# IAQ_Schematic.net
KiCad netlist of a schematic drawn in Altium Designer
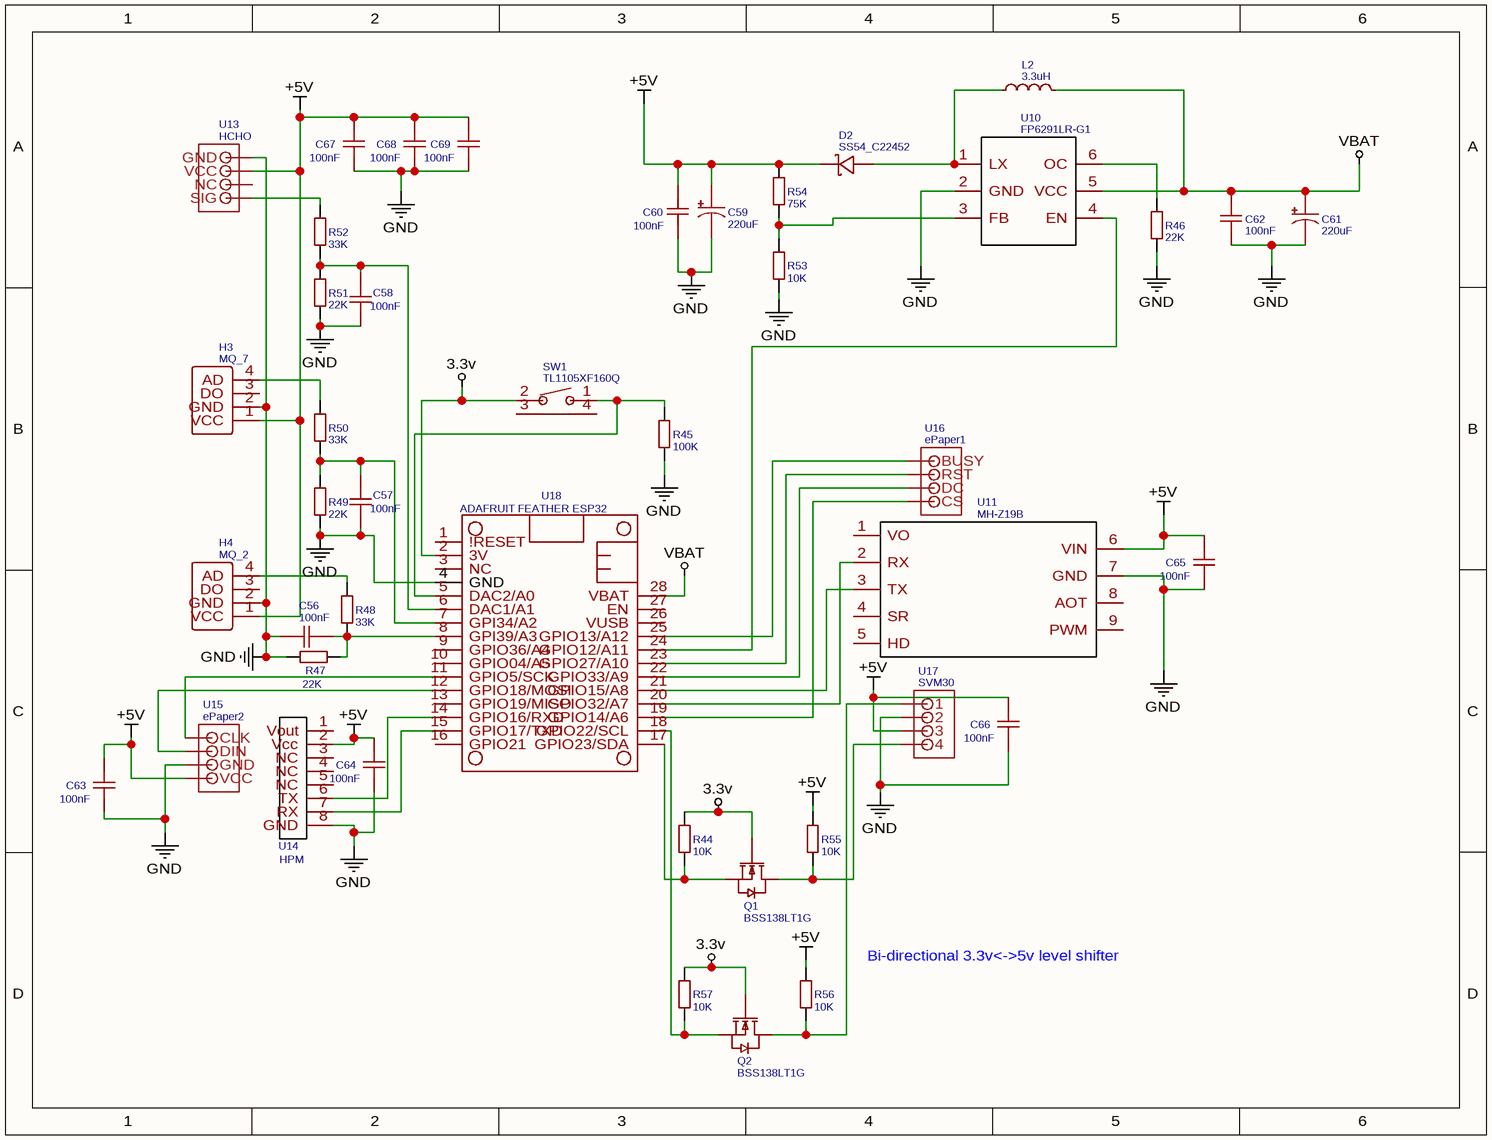
[diagram p0: IAQ_Schematic.schdoc]

(export (version "E")
  (design (tool "Eeschema 10.0.6"))
  (components
    (comp (ref "C56")
      (value "100nF")
      (fields
        (field (name "BOM_MANUFACTURER PART") "CC0603KRX7R9BB104")
        (field (name "BOM_SUPPLIER PART") "C14663")
      )
      (libsource (lib "altium-import") (part "root_0_100nF_"))
    )
    (comp (ref "C57")
      (value "100nF")
      (fields
        (field (name "BOM_MANUFACTURER PART") "CC0603KRX7R9BB104")
        (field (name "BOM_SUPPLIER PART") "C14663")
      )
      (libsource (lib "altium-import") (part "root_1_100nF_"))
    )
    (comp (ref "C58")
      (value "100nF")
      (fields
        (field (name "BOM_MANUFACTURER PART") "CC0603KRX7R9BB104")
        (field (name "BOM_SUPPLIER PART") "C14663")
      )
      (libsource (lib "altium-import") (part "root_1_100nF_"))
    )
    (comp (ref "C59")
      (value "220uF")
      (fields
        (field (name "BOM_MANUFACTURER PART") "VE-221M1HTR-1010")
        (field (name "BOM_SUPPLIER PART") "C134732")
        (field (name "CONTRIBUTOR") "LCSC")
      )
      (libsource (lib "altium-import") (part "root_0_220uF_"))
    )
    (comp (ref "C60")
      (value "100nF")
      (fields
        (field (name "BOM_MANUFACTURER PART") "CC0603KRX7R9BB104")
        (field (name "BOM_SUPPLIER PART") "C14663")
      )
      (libsource (lib "altium-import") (part "root_1_100nF_"))
    )
    (comp (ref "C61")
      (value "220uF")
      (fields
        (field (name "BOM_MANUFACTURER PART") "VE-221M1HTR-1010")
        (field (name "BOM_SUPPLIER PART") "C134732")
        (field (name "CONTRIBUTOR") "LCSC")
      )
      (libsource (lib "altium-import") (part "root_0_220uF_"))
    )
    (comp (ref "C62")
      (value "100nF")
      (fields
        (field (name "BOM_MANUFACTURER PART") "CC0603KRX7R9BB104")
        (field (name "BOM_SUPPLIER PART") "C14663")
      )
      (libsource (lib "altium-import") (part "root_1_100nF_"))
    )
    (comp (ref "C63")
      (value "100nF")
      (fields
        (field (name "BOM_MANUFACTURER PART") "CC0603KRX7R9BB104")
        (field (name "BOM_SUPPLIER PART") "C14663")
      )
      (libsource (lib "altium-import") (part "root_1_100nF_"))
    )
    (comp (ref "C64")
      (value "100nF")
      (fields
        (field (name "BOM_MANUFACTURER PART") "CC0603KRX7R9BB104")
        (field (name "BOM_SUPPLIER PART") "C14663")
      )
      (libsource (lib "altium-import") (part "root_1_100nF_"))
    )
    (comp (ref "C65")
      (value "100nF")
      (fields
        (field (name "BOM_MANUFACTURER PART") "CC0603KRX7R9BB104")
        (field (name "BOM_SUPPLIER PART") "C14663")
      )
      (libsource (lib "altium-import") (part "root_1_100nF_"))
    )
    (comp (ref "C66")
      (value "100nF")
      (fields
        (field (name "BOM_MANUFACTURER PART") "CC0603KRX7R9BB104")
        (field (name "BOM_SUPPLIER PART") "C14663")
      )
      (libsource (lib "altium-import") (part "root_1_100nF_"))
    )
    (comp (ref "C67")
      (value "100nF")
      (fields
        (field (name "BOM_MANUFACTURER PART") "CC0603KRX7R9BB104")
        (field (name "BOM_SUPPLIER PART") "C14663")
      )
      (libsource (lib "altium-import") (part "root_1_100nF_"))
    )
    (comp (ref "C68")
      (value "100nF")
      (fields
        (field (name "BOM_MANUFACTURER PART") "CC0603KRX7R9BB104")
        (field (name "BOM_SUPPLIER PART") "C14663")
      )
      (libsource (lib "altium-import") (part "root_1_100nF_"))
    )
    (comp (ref "C69")
      (value "100nF")
      (fields
        (field (name "BOM_MANUFACTURER PART") "CC0603KRX7R9BB104")
        (field (name "BOM_SUPPLIER PART") "C14663")
      )
      (libsource (lib "altium-import") (part "root_1_100nF_"))
    )
    (comp (ref "D2")
      (value "SS54_C22452")
      (fields (field (name "BOM_MANUFACTURER PART") "SS54") (field (name "BOM_SUPPLIER PART") "C22452"))
      (libsource (lib "altium-import") (part "root_2_SS54_C22452_"))
    )
    (comp (ref "H3")
      (value "MQ_7")
      (fields
        (field (name "BOM_MANUFACTURER PART") "220S-1*4P H=8.5MM Ytype Gold-plated")
        (field (name "BOM_SUPPLIER PART") "C124413")
        (field (name "CONTRIBUTOR") "LCSC")
      )
      (libsource (lib "altium-import") (part "root_2_MQ_7_"))
    )
    (comp (ref "H4")
      (value "MQ_2")
      (fields
        (field (name "BOM_MANUFACTURER PART") "220S-1*4P H=8.5MM Ytype Gold-plated")
        (field (name "BOM_SUPPLIER PART") "C124413")
        (field (name "CONTRIBUTOR") "LCSC")
      )
      (libsource (lib "altium-import") (part "root_2_MQ_2_"))
    )
    (comp (ref "L2")
      (value "3.3uH")
      (fields
        (field (name "BOM_MANUFACTURER PART") "SM1054-3R3MT")
        (field (name "BOM_SUPPLIER PART") "C56605")
      )
      (libsource (lib "altium-import") (part "root_0_3.3uH_"))
    )
    (comp (ref "Q1")
      (value "BSS138LT1G")
      (fields (field (name "BOM_SUPPLIER PART") "C82045"))
      (libsource (lib "altium-import") (part "root_3_BSS138LT1G_"))
    )
    (comp (ref "Q2")
      (value "BSS138LT1G")
      (fields (field (name "BOM_SUPPLIER PART") "C82045"))
      (libsource (lib "altium-import") (part "root_3_BSS138LT1G_"))
    )
    (comp (ref "R44")
      (value "10K")
      (fields
        (field (name "BOM_MANUFACTURER PART") "0603WAF1002T5E")
        (field (name "BOM_SUPPLIER PART") "C25804")
      )
      (libsource (lib "altium-import") (part "root_1_10K_"))
    )
    (comp (ref "R45")
      (value "100K")
      (fields
        (field (name "BOM_MANUFACTURER PART") "0603WAF1003T5E")
        (field (name "BOM_SUPPLIER PART") "C25803")
      )
      (libsource (lib "altium-import") (part "root_1_100K_"))
    )
    (comp (ref "R46")
      (value "22K")
      (fields
        (field (name "BOM_MANUFACTURER PART") "0603WAF2202T5E")
        (field (name "BOM_SUPPLIER PART") "C31850")
      )
      (libsource (lib "altium-import") (part "root_1_22K_"))
    )
    (comp (ref "R47")
      (value "22K")
      (fields
        (field (name "BOM_MANUFACTURER PART") "0603WAF2202T5E")
        (field (name "BOM_SUPPLIER PART") "C31850")
      )
      (libsource (lib "altium-import") (part "root_2_22K_"))
    )
    (comp (ref "R48")
      (value "33K")
      (fields
        (field (name "BOM_MANUFACTURER PART") "0603WAF3302T5E")
        (field (name "BOM_SUPPLIER PART") "C4216")
      )
      (libsource (lib "altium-import") (part "root_1_33K_"))
    )
    (comp (ref "R49")
      (value "22K")
      (fields
        (field (name "BOM_MANUFACTURER PART") "0603WAF2202T5E")
        (field (name "BOM_SUPPLIER PART") "C31850")
      )
      (libsource (lib "altium-import") (part "root_1_22K_"))
    )
    (comp (ref "R50")
      (value "33K")
      (fields
        (field (name "BOM_MANUFACTURER PART") "0603WAF3302T5E")
        (field (name "BOM_SUPPLIER PART") "C4216")
      )
      (libsource (lib "altium-import") (part "root_1_33K_"))
    )
    (comp (ref "R51")
      (value "22K")
      (fields
        (field (name "BOM_MANUFACTURER PART") "0603WAF2202T5E")
        (field (name "BOM_SUPPLIER PART") "C31850")
      )
      (libsource (lib "altium-import") (part "root_1_22K_"))
    )
    (comp (ref "R52")
      (value "33K")
      (fields
        (field (name "BOM_MANUFACTURER PART") "0603WAF3302T5E")
        (field (name "BOM_SUPPLIER PART") "C4216")
      )
      (libsource (lib "altium-import") (part "root_1_33K_"))
    )
    (comp (ref "R53")
      (value "10K")
      (fields
        (field (name "BOM_MANUFACTURER PART") "0603WAF1002T5E")
        (field (name "BOM_SUPPLIER PART") "C25804")
      )
      (libsource (lib "altium-import") (part "root_1_10K_"))
    )
    (comp (ref "R54")
      (value "75K")
      (fields
        (field (name "BOM_MANUFACTURER PART") "0603WAF7502T5E")
        (field (name "BOM_SUPPLIER PART") "C23242")
      )
      (libsource (lib "altium-import") (part "root_1_75K_"))
    )
    (comp (ref "R55")
      (value "10K")
      (fields
        (field (name "BOM_MANUFACTURER PART") "0603WAF1002T5E")
        (field (name "BOM_SUPPLIER PART") "C25804")
      )
      (libsource (lib "altium-import") (part "root_1_10K_"))
    )
    (comp (ref "R56")
      (value "10K")
      (fields
        (field (name "BOM_MANUFACTURER PART") "0603WAF1002T5E")
        (field (name "BOM_SUPPLIER PART") "C25804")
      )
      (libsource (lib "altium-import") (part "root_1_10K_"))
    )
    (comp (ref "R57")
      (value "10K")
      (fields
        (field (name "BOM_MANUFACTURER PART") "0603WAF1002T5E")
        (field (name "BOM_SUPPLIER PART") "C25804")
      )
      (libsource (lib "altium-import") (part "root_1_10K_"))
    )
    (comp (ref "SW1")
      (value "TL1105XF160Q")
      (fields (field (name "BOM_SUPPLIER PART") "C273492") (field (name "CONTRIBUTOR") "LCSC"))
      (libsource (lib "altium-import") (part "root_0_TL1105XF160Q_"))
    )
    (comp (ref "U10")
      (value "FP6291LR-G1")
      (fields (field (name "BOM_SUPPLIER PART") "C18701"))
      (libsource (lib "altium-import") (part "root_0_FP6291LR-G1_"))
    )
    (comp (ref "U11")
      (value "MH-Z19B")
      (fields (field (name "CONTRIBUTOR") "Egor Avksentyev"))
      (libsource (lib "altium-import") (part "root_2_MH-Z19B_"))
    )
    (comp (ref "U13") (value "HCHO") (libsource (lib "altium-import") (part "root_2_HCHO_")))
    (comp (ref "U14")
      (value "HPM")
      (fields
        (field (name "BOM_MANUFACTURER PART") "0530470810")
        (field (name "BOM_SUPPLIER PART") "WM1737-ND")
        (field (name "CONTRIBUTOR") "CT_Engr")
      )
      (libsource (lib "altium-import") (part "root_3_HPM_"))
    )
    (comp (ref "U15") (value "ePaper2") (libsource (lib "altium-import") (part "root_0_ePaper2_")))
    (comp (ref "U16") (value "ePaper1") (libsource (lib "altium-import") (part "root_0_ePaper1_")))
    (comp (ref "U17") (value "SVM30") (libsource (lib "altium-import") (part "root_0_SVM30_")))
    (comp (ref "U18")
      (value "ADAFRUIT FEATHER ESP32")
      (libsource (lib "altium-import") (part "root_0_ADAFRUIT FEATHER ESP32_"))
    )
  )
  (nets
    (net (code "1") (name "+5V") (class "Default")
      (node (ref "C59") (pin "1") (pinfunction "1_1") (pintype "passive"))
      (node (ref "C60") (pin "2") (pinfunction "2_2") (pintype "passive"))
      (node (ref "C63") (pin "2") (pinfunction "2_2") (pintype "passive"))
      (node (ref "C64") (pin "2") (pinfunction "2_2") (pintype "passive"))
      (node (ref "C65") (pin "2") (pinfunction "2_2") (pintype "passive"))
      (node (ref "C66") (pin "2") (pinfunction "2_2") (pintype "passive"))
      (node (ref "C67") (pin "2") (pinfunction "2_2") (pintype "passive"))
      (node (ref "C68") (pin "2") (pinfunction "2_2") (pintype "passive"))
      (node (ref "C69") (pin "2") (pinfunction "2_2") (pintype "passive"))
      (node (ref "D2") (pin "2") (pinfunction "K_2") (pintype "passive"))
      (node (ref "H3") (pin "1") (pinfunction "VCC_1") (pintype "passive"))
      (node (ref "H4") (pin "1") (pinfunction "VCC_1") (pintype "passive"))
      (node (ref "R54") (pin "2") (pinfunction "2_2") (pintype "passive"))
      (node (ref "R55") (pin "2") (pinfunction "2_2") (pintype "passive"))
      (node (ref "R56") (pin "2") (pinfunction "2_2") (pintype "passive"))
      (node (ref "U11") (pin "6") (pinfunction "VIN_6") (pintype "passive"))
      (node (ref "U13") (pin "P3") (pinfunction "VCC_P3") (pintype "passive"))
      (node (ref "U14") (pin "2") (pinfunction "Vcc_2") (pintype "passive"))
      (node (ref "U15") (pin "P4") (pinfunction "VCC_P4") (pintype "passive"))
      (node (ref "U17") (pin "P3") (pinfunction "3_P3") (pintype "passive"))
    )
    (net (code "2") (name "3.3v") (class "Default")
      (node (ref "Q1") (pin "1") (pinfunction "G_1") (pintype "passive"))
      (node (ref "Q2") (pin "1") (pinfunction "G_1") (pintype "passive"))
      (node (ref "R44") (pin "2") (pinfunction "2_2") (pintype "passive"))
      (node (ref "R57") (pin "2") (pinfunction "2_2") (pintype "passive"))
      (node (ref "SW1") (pin "2") (pinfunction "2_2") (pintype "passive"))
      (node (ref "U18") (pin "2") (pinfunction "3V_2") (pintype "passive"))
    )
    (net (code "3") (name "GND") (class "Default")
      (node (ref "C56") (pin "1") (pinfunction "1_1") (pintype "passive"))
      (node (ref "C57") (pin "1") (pinfunction "1_1") (pintype "passive"))
      (node (ref "C58") (pin "1") (pinfunction "1_1") (pintype "passive"))
      (node (ref "C59") (pin "2") (pinfunction "2_2") (pintype "passive"))
      (node (ref "C60") (pin "1") (pinfunction "1_1") (pintype "passive"))
      (node (ref "C61") (pin "2") (pinfunction "2_2") (pintype "passive"))
      (node (ref "C62") (pin "1") (pinfunction "1_1") (pintype "passive"))
      (node (ref "C63") (pin "1") (pinfunction "1_1") (pintype "passive"))
      (node (ref "C64") (pin "1") (pinfunction "1_1") (pintype "passive"))
      (node (ref "C65") (pin "1") (pinfunction "1_1") (pintype "passive"))
      (node (ref "C66") (pin "1") (pinfunction "1_1") (pintype "passive"))
      (node (ref "C67") (pin "1") (pinfunction "1_1") (pintype "passive"))
      (node (ref "C68") (pin "1") (pinfunction "1_1") (pintype "passive"))
      (node (ref "C69") (pin "1") (pinfunction "1_1") (pintype "passive"))
      (node (ref "H3") (pin "2") (pinfunction "GND_2") (pintype "passive"))
      (node (ref "H4") (pin "2") (pinfunction "GND_2") (pintype "passive"))
      (node (ref "R45") (pin "1") (pinfunction "1_1") (pintype "passive"))
      (node (ref "R46") (pin "1") (pinfunction "1_1") (pintype "passive"))
      (node (ref "R47") (pin "2") (pinfunction "2_2") (pintype "passive"))
      (node (ref "R49") (pin "1") (pinfunction "1_1") (pintype "passive"))
      (node (ref "R51") (pin "1") (pinfunction "1_1") (pintype "passive"))
      (node (ref "R53") (pin "1") (pinfunction "1_1") (pintype "passive"))
      (node (ref "U10") (pin "2") (pinfunction "GND_2") (pintype "passive"))
      (node (ref "U11") (pin "7") (pinfunction "GND_7") (pintype "passive"))
      (node (ref "U13") (pin "P4") (pinfunction "GND_P4") (pintype "passive"))
      (node (ref "U14") (pin "8") (pinfunction "GND_8") (pintype "passive"))
      (node (ref "U15") (pin "P3") (pinfunction "GND_P3") (pintype "passive"))
      (node (ref "U17") (pin "P2") (pinfunction "2_P2") (pintype "passive"))
      (node (ref "U18") (pin "4") (pinfunction "GND_4") (pintype "passive"))
    )
    (net (code "4") (name "Net-(D2-A)") (class "Default")
      (node (ref "D2") (pin "1") (pinfunction "A_1") (pintype "passive"))
      (node (ref "L2") (pin "1") (pinfunction "1_1") (pintype "passive"))
      (node (ref "U10") (pin "1") (pinfunction "LX_1") (pintype "passive"))
    )
    (net (code "5") (name "Net-(H3-AD)") (class "Default")
      (node (ref "H3") (pin "4") (pinfunction "AD_4") (pintype "passive"))
      (node (ref "R50") (pin "2") (pinfunction "2_2") (pintype "passive"))
    )
    (net (code "6") (name "Net-(H4-AD)") (class "Default")
      (node (ref "H4") (pin "4") (pinfunction "AD_4") (pintype "passive"))
      (node (ref "R48") (pin "2") (pinfunction "2_2") (pintype "passive"))
    )
    (net (code "7") (name "Net-(Q1-D)") (class "Default")
      (node (ref "Q1") (pin "3") (pinfunction "D_3") (pintype "passive"))
      (node (ref "R55") (pin "1") (pinfunction "1_1") (pintype "passive"))
      (node (ref "U17") (pin "P4") (pinfunction "4_P4") (pintype "passive"))
    )
    (net (code "8") (name "Net-(Q1-S)") (class "Default")
      (node (ref "Q1") (pin "2") (pinfunction "S_2") (pintype "passive"))
      (node (ref "R44") (pin "1") (pinfunction "1_1") (pintype "passive"))
      (node (ref "U18") (pin "17") (pinfunction "GPIO23/SDA_17") (pintype "passive"))
    )
    (net (code "9") (name "Net-(Q2-D)") (class "Default")
      (node (ref "Q2") (pin "3") (pinfunction "D_3") (pintype "passive"))
      (node (ref "R56") (pin "1") (pinfunction "1_1") (pintype "passive"))
      (node (ref "U17") (pin "P1") (pinfunction "1_P1") (pintype "passive"))
    )
    (net (code "10") (name "Net-(Q2-S)") (class "Default")
      (node (ref "Q2") (pin "2") (pinfunction "S_2") (pintype "passive"))
      (node (ref "R57") (pin "1") (pinfunction "1_1") (pintype "passive"))
      (node (ref "U18") (pin "18") (pinfunction "GPIO22/SCL_18") (pintype "passive"))
    )
    (net (code "11") (name "Net-(U10-EN)") (class "Default")
      (node (ref "U10") (pin "4") (pinfunction "EN_4") (pintype "passive"))
      (node (ref "U18") (pin "24") (pinfunction "GPIO12/A11_24") (pintype "passive"))
    )
    (net (code "12") (name "Net-(U10-FB)") (class "Default")
      (node (ref "R53") (pin "2") (pinfunction "2_2") (pintype "passive"))
      (node (ref "R54") (pin "1") (pinfunction "1_1") (pintype "passive"))
      (node (ref "U10") (pin "3") (pinfunction "FB_3") (pintype "passive"))
    )
    (net (code "13") (name "Net-(U10-OC)") (class "Default")
      (node (ref "R46") (pin "2") (pinfunction "2_2") (pintype "passive"))
      (node (ref "U10") (pin "6") (pinfunction "OC_6") (pintype "passive"))
    )
    (net (code "14") (name "Net-(U11-RX)") (class "Default")
      (node (ref "U11") (pin "2") (pinfunction "RX_2") (pintype "passive"))
      (node (ref "U18") (pin "20") (pinfunction "GPIO32/A7_20") (pintype "passive"))
    )
    (net (code "15") (name "Net-(U11-TX)") (class "Default")
      (node (ref "U11") (pin "3") (pinfunction "TX_3") (pintype "passive"))
      (node (ref "U18") (pin "21") (pinfunction "GPIO15/A8_21") (pintype "passive"))
    )
    (net (code "16") (name "Net-(U13-SIG)") (class "Default")
      (node (ref "R52") (pin "2") (pinfunction "2_2") (pintype "passive"))
      (node (ref "U13") (pin "P1") (pinfunction "SIG_P1") (pintype "passive"))
    )
    (net (code "17") (name "Net-(U14-RX)") (class "Default")
      (node (ref "U14") (pin "7") (pinfunction "RX_7") (pintype "passive"))
      (node (ref "U18") (pin "15") (pinfunction "GPIO17/TXD_15") (pintype "passive"))
    )
    (net (code "18") (name "Net-(U14-TX)") (class "Default")
      (node (ref "U14") (pin "6") (pinfunction "TX_6") (pintype "passive"))
      (node (ref "U18") (pin "14") (pinfunction "GPIO16/RXD_14") (pintype "passive"))
    )
    (net (code "19") (name "Net-(U15-CLK)") (class "Default")
      (node (ref "U15") (pin "P1") (pinfunction "CLK_P1") (pintype "passive"))
      (node (ref "U18") (pin "11") (pinfunction "GPIO5/SCK_11") (pintype "passive"))
    )
    (net (code "20") (name "Net-(U15-DIN)") (class "Default")
      (node (ref "U15") (pin "P2") (pinfunction "DIN_P2") (pintype "passive"))
      (node (ref "U18") (pin "12") (pinfunction "GPIO18/MOSI_12") (pintype "passive"))
    )
    (net (code "21") (name "Net-(U16-BUSY)") (class "Default")
      (node (ref "U16") (pin "P1") (pinfunction "BUSY_P1") (pintype "passive"))
      (node (ref "U18") (pin "25") (pinfunction "GPIO13/A12_25") (pintype "passive"))
    )
    (net (code "22") (name "Net-(U16-CS)") (class "Default")
      (node (ref "U16") (pin "P4") (pinfunction "CS_P4") (pintype "passive"))
      (node (ref "U18") (pin "19") (pinfunction "GPIO14/A6_19") (pintype "passive"))
    )
    (net (code "23") (name "Net-(U16-DC)") (class "Default")
      (node (ref "U16") (pin "P3") (pinfunction "DC_P3") (pintype "passive"))
      (node (ref "U18") (pin "22") (pinfunction "GPIO33/A9_22") (pintype "passive"))
    )
    (net (code "24") (name "Net-(U16-RST)") (class "Default")
      (node (ref "U16") (pin "P2") (pinfunction "RST_P2") (pintype "passive"))
      (node (ref "U18") (pin "23") (pinfunction "GPIO27/A10_23") (pintype "passive"))
    )
    (net (code "25") (name "Net-(U18-DAC1{slash}A1)") (class "Default")
      (node (ref "C58") (pin "2") (pinfunction "2_2") (pintype "passive"))
      (node (ref "R51") (pin "2") (pinfunction "2_2") (pintype "passive"))
      (node (ref "R52") (pin "1") (pinfunction "1_1") (pintype "passive"))
      (node (ref "U18") (pin "6") (pinfunction "DAC1/A1_6") (pintype "passive"))
    )
    (net (code "26") (name "Net-(U18-DAC2{slash}A0)") (class "Default")
      (node (ref "R45") (pin "2") (pinfunction "2_2") (pintype "passive"))
      (node (ref "SW1") (pin "1") (pinfunction "1_1") (pintype "passive"))
      (node (ref "U18") (pin "5") (pinfunction "DAC2/A0_5") (pintype "passive"))
    )
    (net (code "27") (name "Net-(U18-GPI34{slash}A2)") (class "Default")
      (node (ref "C57") (pin "2") (pinfunction "2_2") (pintype "passive"))
      (node (ref "R49") (pin "2") (pinfunction "2_2") (pintype "passive"))
      (node (ref "R50") (pin "1") (pinfunction "1_1") (pintype "passive"))
      (node (ref "U18") (pin "7") (pinfunction "GPI34/A2_7") (pintype "passive"))
    )
    (net (code "28") (name "Net-(U18-GPI39{slash}A3)") (class "Default")
      (node (ref "C56") (pin "2") (pinfunction "2_2") (pintype "passive"))
      (node (ref "R47") (pin "1") (pinfunction "1_1") (pintype "passive"))
      (node (ref "R48") (pin "1") (pinfunction "1_1") (pintype "passive"))
      (node (ref "U18") (pin "8") (pinfunction "GPI39/A3_8") (pintype "passive"))
    )
    (net (code "29") (name "VBAT") (class "Default")
      (node (ref "C61") (pin "1") (pinfunction "1_1") (pintype "passive"))
      (node (ref "C62") (pin "2") (pinfunction "2_2") (pintype "passive"))
      (node (ref "L2") (pin "2") (pinfunction "2_2") (pintype "passive"))
      (node (ref "U10") (pin "5") (pinfunction "VCC_5") (pintype "passive"))
      (node (ref "U18") (pin "28") (pinfunction "VBAT_28") (pintype "passive"))
    )
    (net (code "30") (name "unconnected-(H3-DO-Pad3)") (class "Default")
      (node (ref "H3") (pin "3") (pinfunction "DO_3") (pintype "passive"))
    )
    (net (code "31") (name "unconnected-(H4-DO-Pad3)") (class "Default")
      (node (ref "H4") (pin "3") (pinfunction "DO_3") (pintype "passive"))
    )
    (net (code "32") (name "unconnected-(SW1-Pad3)") (class "Default")
      (node (ref "SW1") (pin "3") (pinfunction "3_3") (pintype "passive"))
    )
    (net (code "33") (name "unconnected-(SW1-Pad4)") (class "Default")
      (node (ref "SW1") (pin "4") (pinfunction "4_4") (pintype "passive"))
    )
    (net (code "34") (name "unconnected-(U11-AOT-Pad8)") (class "Default")
      (node (ref "U11") (pin "8") (pinfunction "AOT_8") (pintype "passive"))
    )
    (net (code "35") (name "unconnected-(U11-HD-Pad5)") (class "Default")
      (node (ref "U11") (pin "5") (pinfunction "HD_5") (pintype "passive"))
    )
    (net (code "36") (name "unconnected-(U11-PWM-Pad9)") (class "Default")
      (node (ref "U11") (pin "9") (pinfunction "PWM_9") (pintype "passive"))
    )
    (net (code "37") (name "unconnected-(U11-SR-Pad4)") (class "Default")
      (node (ref "U11") (pin "4") (pinfunction "SR_4") (pintype "passive"))
    )
    (net (code "38") (name "unconnected-(U11-VO-Pad1)") (class "Default")
      (node (ref "U11") (pin "1") (pinfunction "VO_1") (pintype "passive"))
    )
    (net (code "39") (name "unconnected-(U13-NC-PadP2)") (class "Default")
      (node (ref "U13") (pin "P2") (pinfunction "NC_P2") (pintype "passive"))
    )
    (net (code "40") (name "unconnected-(U14-NC-Pad3)") (class "Default")
      (node (ref "U14") (pin "3") (pinfunction "NC_3") (pintype "passive"))
    )
    (net (code "41") (name "unconnected-(U14-NC-Pad4)") (class "Default")
      (node (ref "U14") (pin "4") (pinfunction "NC_4") (pintype "passive"))
    )
    (net (code "42") (name "unconnected-(U14-NC-Pad5)") (class "Default")
      (node (ref "U14") (pin "5") (pinfunction "NC_5") (pintype "passive"))
    )
    (net (code "43") (name "unconnected-(U14-Vout-Pad1)") (class "Default")
      (node (ref "U14") (pin "1") (pinfunction "Vout_1") (pintype "passive"))
    )
    (net (code "44") (name "unconnected-(U18-!RESET-Pad1)") (class "Default")
      (node (ref "U18") (pin "1") (pinfunction "!RESET_1") (pintype "passive"))
    )
    (net (code "45") (name "unconnected-(U18-EN-Pad27)") (class "Default")
      (node (ref "U18") (pin "27") (pinfunction "EN_27") (pintype "passive"))
    )
    (net (code "46") (name "unconnected-(U18-GPIO04{slash}A5-Pad10)") (class "Default")
      (node (ref "U18") (pin "10") (pinfunction "GPIO04/A5_10") (pintype "passive"))
    )
    (net (code "47") (name "unconnected-(U18-GPIO19{slash}MISO-Pad13)") (class "Default")
      (node (ref "U18") (pin "13") (pinfunction "GPIO19/MISO_13") (pintype "passive"))
    )
    (net (code "48") (name "unconnected-(U18-GPIO21-Pad16)") (class "Default")
      (node (ref "U18") (pin "16") (pinfunction "GPIO21_16") (pintype "passive"))
    )
    (net (code "49") (name "unconnected-(U18-GPIO36{slash}A4-Pad9)") (class "Default")
      (node (ref "U18") (pin "9") (pinfunction "GPIO36/A4_9") (pintype "passive"))
    )
    (net (code "50") (name "unconnected-(U18-NC-Pad3)") (class "Default")
      (node (ref "U18") (pin "3") (pinfunction "NC_3") (pintype "passive"))
    )
    (net (code "51") (name "unconnected-(U18-VUSB-Pad26)") (class "Default")
      (node (ref "U18") (pin "26") (pinfunction "VUSB_26") (pintype "passive"))
    )
  )
)
